# KRP_SMproject_2.net
KiCad netlist of a schematic drawn in EAGLE
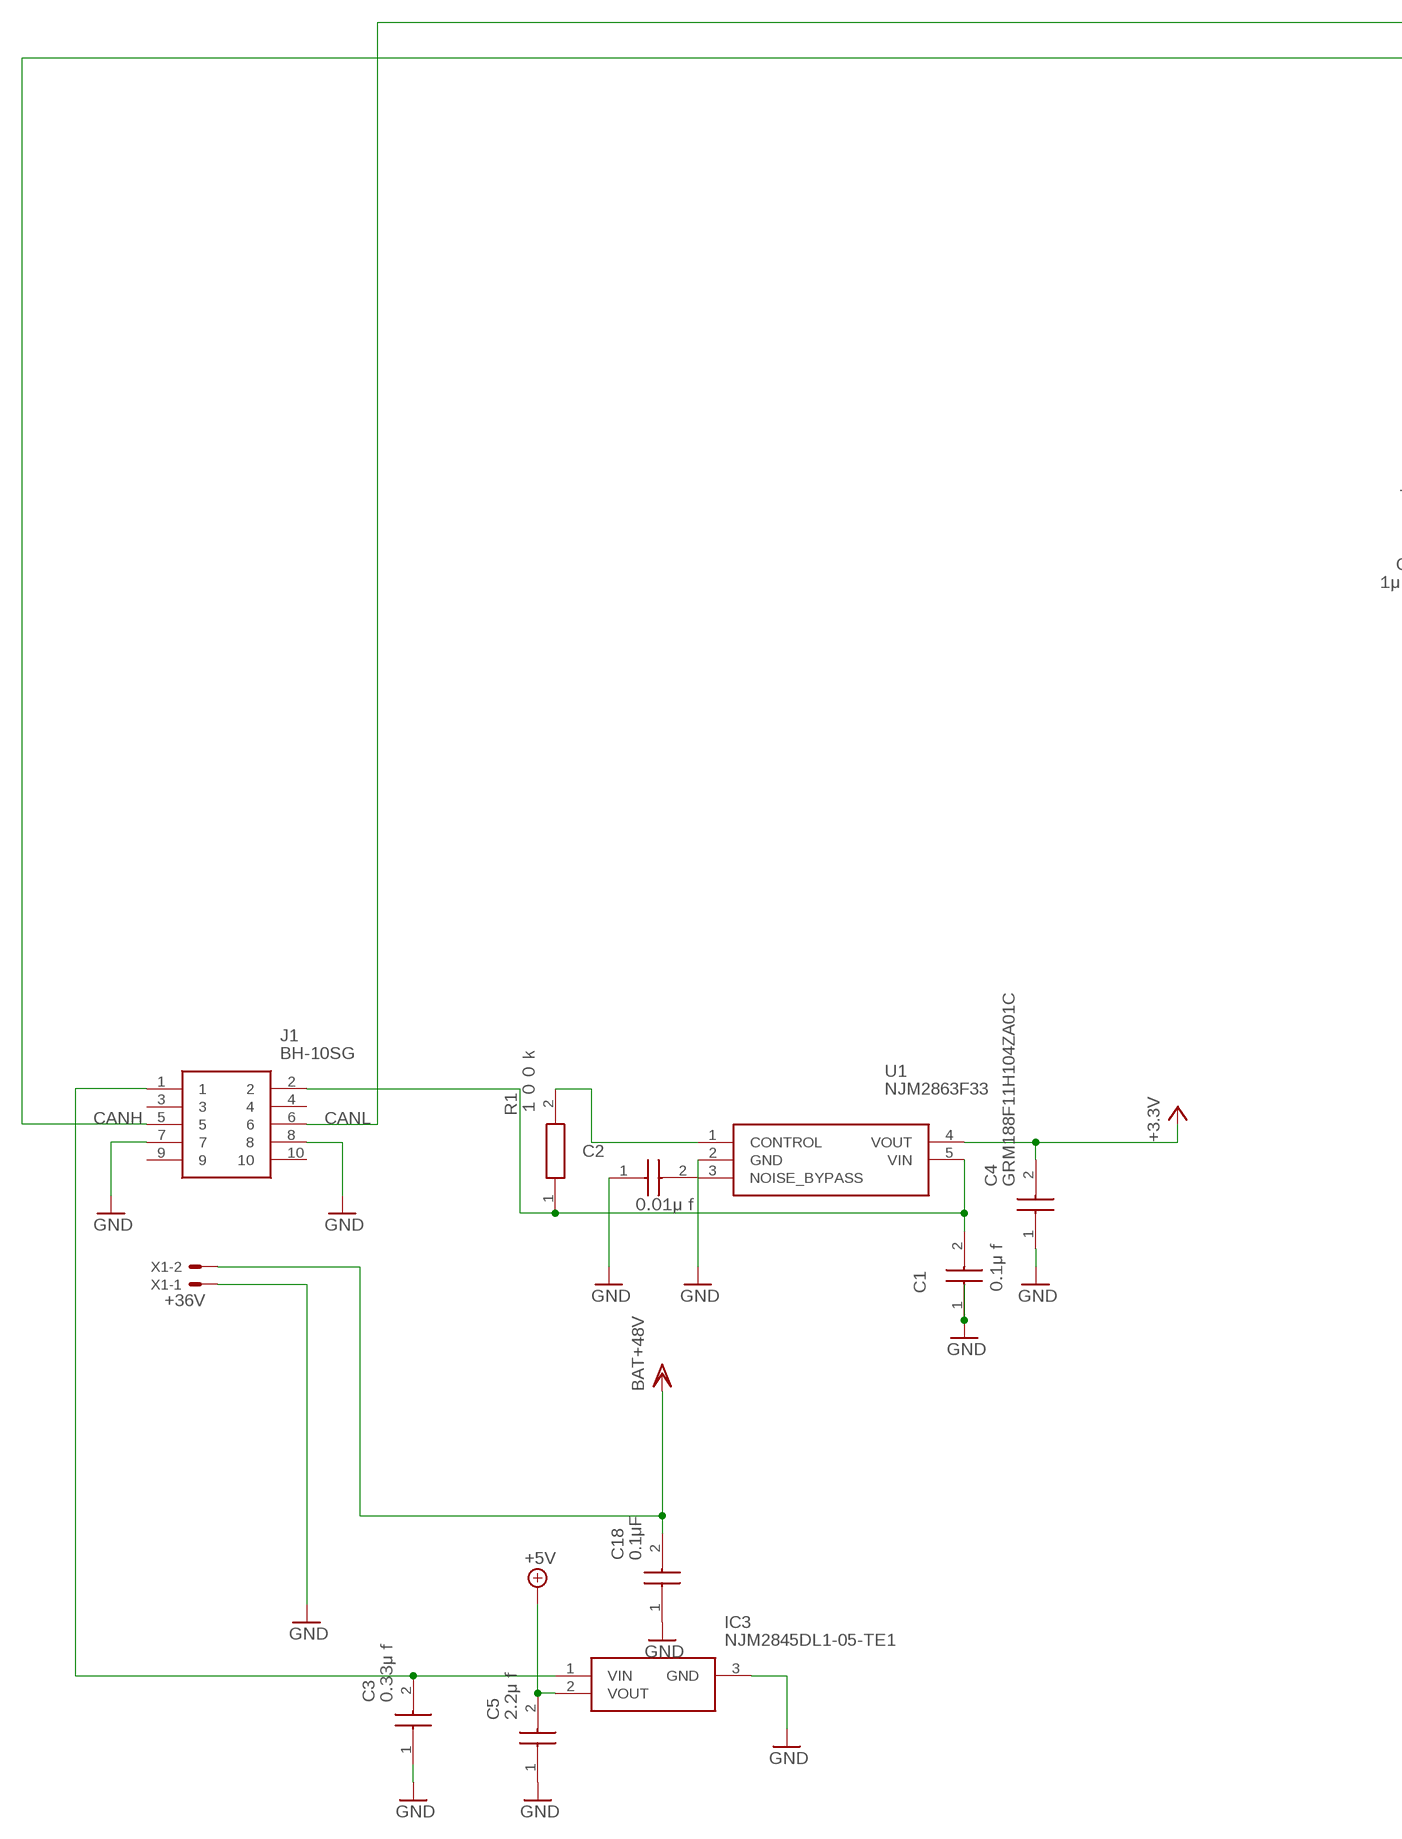
[diagram p0: schematic, sheet 1, part 1 of 2]
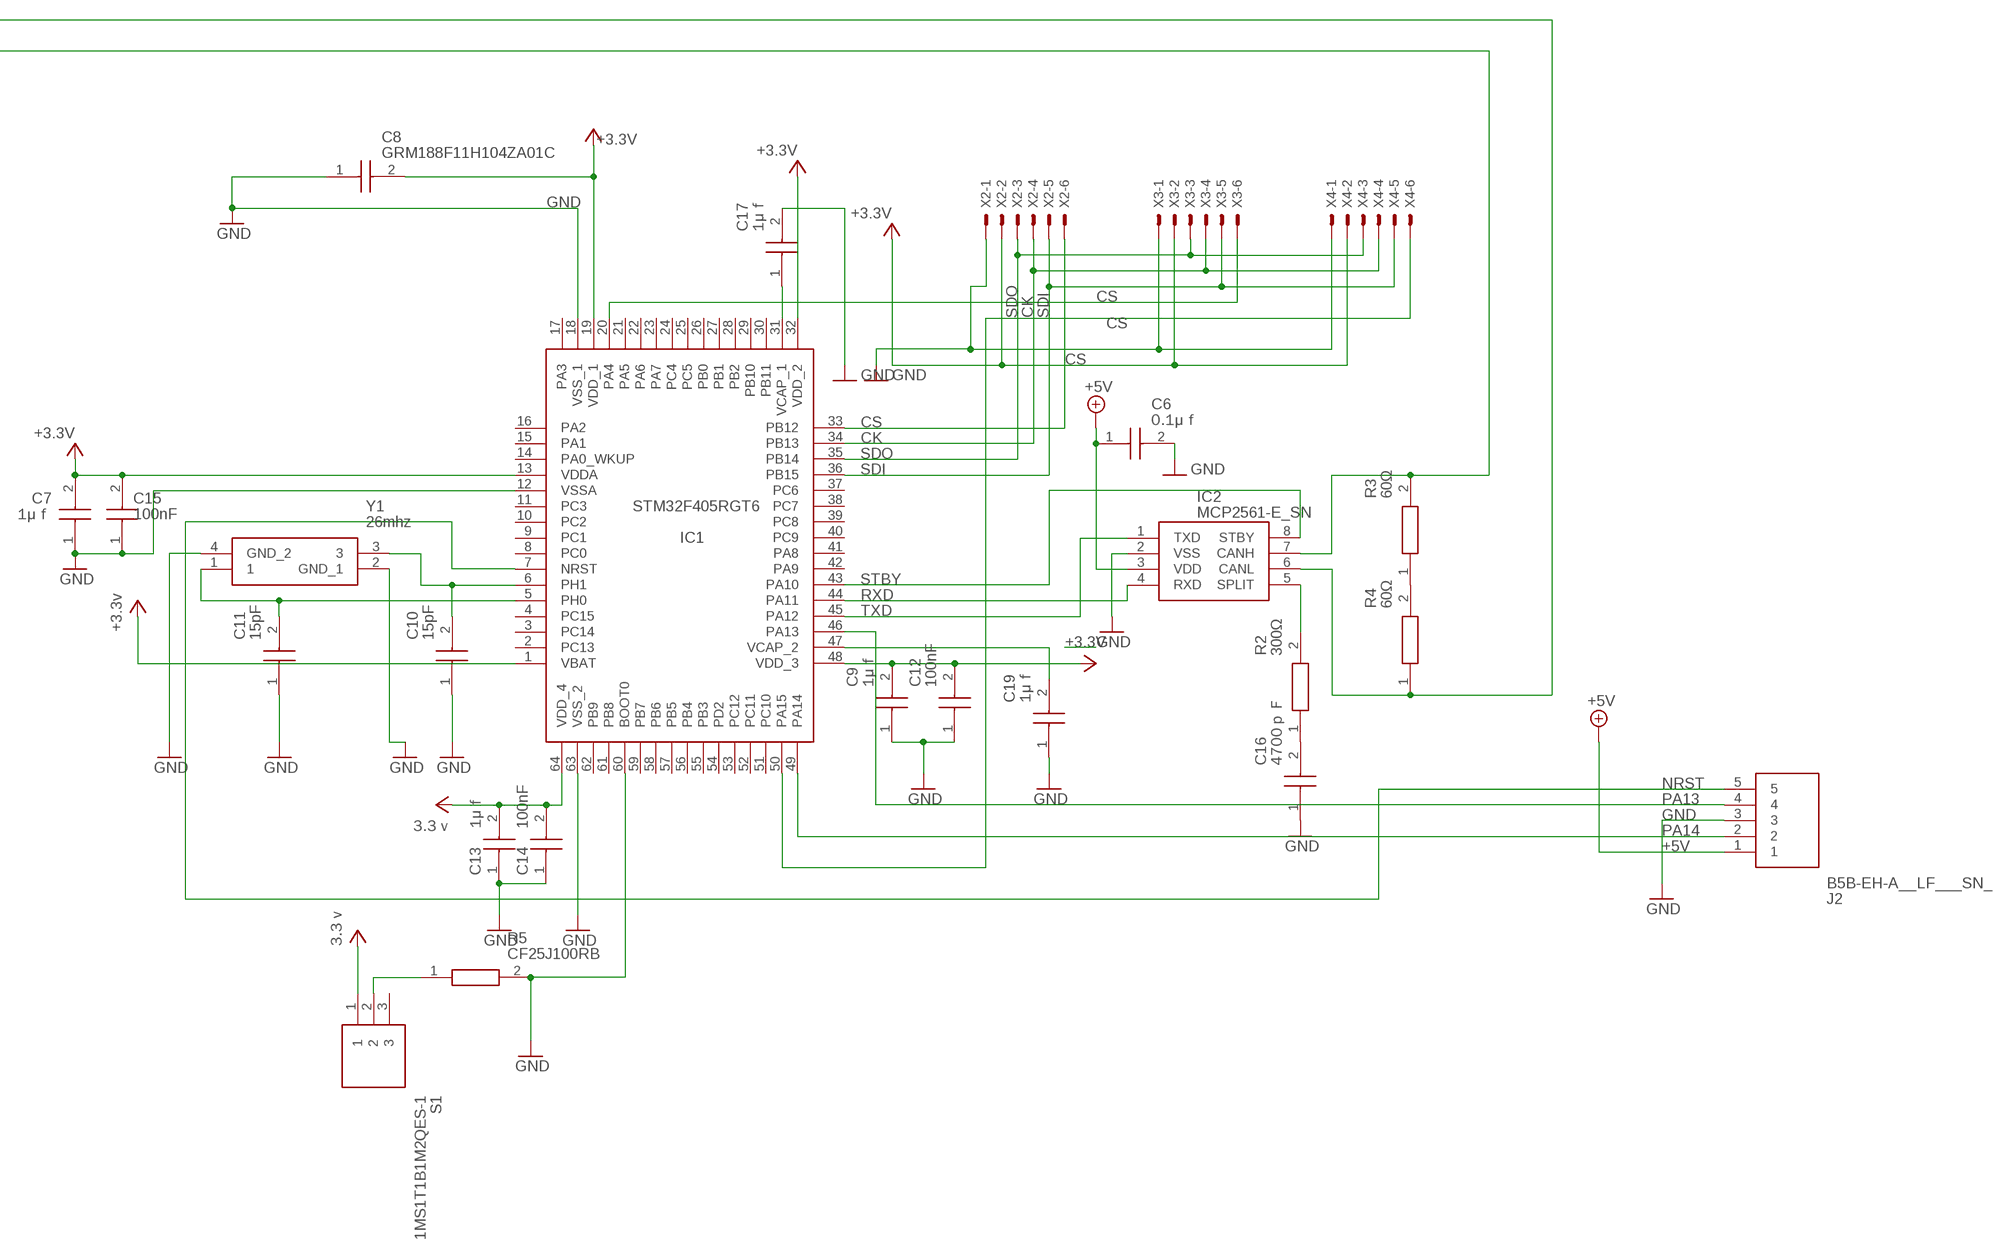
[diagram p1: schematic, sheet 1, part 2 of 2]

(export (version "E")
  (design (tool "Eeschema 10.0.6"))
  (components
    (comp (ref "C1")
      (value "0.1μｆ")
      (footprint "eagle-import:CAPC1608X90N")
      (fields (field (name "MANUFACTURER_PART_NUMBER") "GRM188F11H104ZA01C"))
      (libsource (lib "eagle-import") (part "GRM188F11H104ZA01C"))
    )
    (comp (ref "C2")
      (value "0.01μｆ")
      (footprint "eagle-import:CAPC1608X90N")
      (fields (field (name "MANUFACTURER_PART_NUMBER") "GRM188F11H104ZA01C"))
      (libsource (lib "eagle-import") (part "GRM188F11H104ZA01C"))
    )
    (comp (ref "C3")
      (value "0.33μｆ")
      (footprint "eagle-import:CAPC1608X90N")
      (fields (field (name "MANUFACTURER_PART_NUMBER") "GRM188F11H104ZA01C"))
      (libsource (lib "eagle-import") (part "GRM188F11H104ZA01C"))
    )
    (comp (ref "C4")
      (value "GRM188F11H104ZA01C")
      (footprint "eagle-import:CAPC1608X90N")
      (libsource (lib "eagle-import") (part "GRM188F11H104ZA01C"))
    )
    (comp (ref "C5")
      (value "2.2μｆ")
      (footprint "eagle-import:CAPC1608X90N")
      (fields (field (name "MANUFACTURER_PART_NUMBER") "GRM188F11H104ZA01C"))
      (libsource (lib "eagle-import") (part "GRM188F11H104ZA01C"))
    )
    (comp (ref "C6")
      (value "0.1μｆ")
      (footprint "eagle-import:CAPC1608X90N")
      (fields (field (name "MANUFACTURER_PART_NUMBER") "GRM188F11H104ZA01C"))
      (libsource (lib "eagle-import") (part "GRM188F11H104ZA01C"))
    )
    (comp (ref "C7")
      (value "1μｆ")
      (footprint "eagle-import:CAPC1608X90N")
      (fields (field (name "MANUFACTURER_PART_NUMBER") "GRM188F11H104ZA01C"))
      (libsource (lib "eagle-import") (part "GRM188F11H104ZA01C"))
    )
    (comp (ref "C8")
      (value "GRM188F11H104ZA01C")
      (footprint "eagle-import:CAPC1608X90N")
      (libsource (lib "eagle-import") (part "GRM188F11H104ZA01C"))
    )
    (comp (ref "C9")
      (value "1μｆ")
      (footprint "eagle-import:CAPC1608X90N")
      (fields (field (name "MANUFACTURER_PART_NUMBER") "GRM188F11H104ZA01C"))
      (libsource (lib "eagle-import") (part "GRM188F11H104ZA01C"))
    )
    (comp (ref "C10")
      (value "15pF")
      (footprint "eagle-import:CAPC1608X90N")
      (fields (field (name "MANUFACTURER_PART_NUMBER") "GRM188F11H104ZA01C"))
      (libsource (lib "eagle-import") (part "GRM188F11H104ZA01C"))
    )
    (comp (ref "C11")
      (value "15pF")
      (footprint "eagle-import:CAPC1608X90N")
      (fields (field (name "MANUFACTURER_PART_NUMBER") "GRM188F11H104ZA01C"))
      (libsource (lib "eagle-import") (part "GRM188F11H104ZA01C"))
    )
    (comp (ref "C12")
      (value "100nF")
      (footprint "eagle-import:CAPC1608X90N")
      (fields (field (name "MANUFACTURER_PART_NUMBER") "GRM188F11H104ZA01C"))
      (libsource (lib "eagle-import") (part "GRM188F11H104ZA01C"))
    )
    (comp (ref "C13")
      (value "1μｆ")
      (footprint "eagle-import:CAPC1608X90N")
      (fields (field (name "MANUFACTURER_PART_NUMBER") "GRM188F11H104ZA01C"))
      (libsource (lib "eagle-import") (part "GRM188F11H104ZA01C"))
    )
    (comp (ref "C14")
      (value "100nF")
      (footprint "eagle-import:CAPC1608X90N")
      (fields (field (name "MANUFACTURER_PART_NUMBER") "GRM188F11H104ZA01C"))
      (libsource (lib "eagle-import") (part "GRM188F11H104ZA01C"))
    )
    (comp (ref "C15")
      (value "100nF")
      (footprint "eagle-import:CAPC1608X90N")
      (fields (field (name "MANUFACTURER_PART_NUMBER") "GRM188F11H104ZA01C"))
      (libsource (lib "eagle-import") (part "GRM188F11H104ZA01C"))
    )
    (comp (ref "C16")
      (value "4700ｐＦ")
      (footprint "eagle-import:CAPC1608X90N")
      (fields (field (name "MANUFACTURER_PART_NUMBER") "GRM188F11H104ZA01C"))
      (libsource (lib "eagle-import") (part "GRM188F11H104ZA01C"))
    )
    (comp (ref "C17")
      (value "1μｆ")
      (footprint "eagle-import:CAPC1608X90N")
      (fields (field (name "MANUFACTURER_PART_NUMBER") "GRM188F11H104ZA01C"))
      (libsource (lib "eagle-import") (part "GRM188F11H104ZA01C"))
    )
    (comp (ref "C18")
      (value "0.1μF")
      (footprint "eagle-import:CAPC1608X90N")
      (fields (field (name "MANUFACTURER_PART_NUMBER") "GRM188F11H104ZA01C"))
      (libsource (lib "eagle-import") (part "GRM188F11H104ZA01C"))
    )
    (comp (ref "C19")
      (value "1μｆ")
      (footprint "eagle-import:CAPC1608X90N")
      (fields (field (name "MANUFACTURER_PART_NUMBER") "GRM188F11H104ZA01C"))
      (libsource (lib "eagle-import") (part "GRM188F11H104ZA01C"))
    )
    (comp (ref "IC1")
      (value "STM32F405RGT6")
      (footprint "eagle-import:QFP50P1200X1200X160-64N")
      (fields (field (name "RS_PART_NUMBER") "7468217P"))
      (libsource (lib "eagle-import") (part "STM32F405RGT6"))
    )
    (comp (ref "IC2")
      (value "MCP2561-E_SN")
      (footprint "eagle-import:SOIC127P600X175-8N")
      (fields
        (field (name "MANUFACTURER_PART_NUMBER") "MCP2561-E/SN")
        (field (name "RS_PART_NUMBER") "7990216P")
      )
      (libsource (lib "eagle-import") (part "MCP2561-E_SN"))
    )
    (comp (ref "IC3")
      (value "NJM2845DL1-05-TE1")
      (footprint "eagle-import:TO-252-3-L1")
      (libsource (lib "eagle-import") (part "NJM2845DL1-05-TE1"))
    )
    (comp (ref "J1")
      (value "BH-10SG")
      (footprint "eagle-import:SHDR10W64P254_2X5_2032X910X935")
      (libsource (lib "eagle-import") (part "BH-10SG"))
    )
    (comp (ref "J2")
      (value "B5B-EH-A__LF___SN_")
      (footprint "eagle-import:SHDR5W64P0X250_1X5_1500X380X60")
      (fields
        (field (name "MANUFACTURER_PART_NUMBER") "B5B-EH-A (LF) (SN)")
        (field (name "RS_PART_NUMBER") "5151412P")
      )
      (libsource (lib "eagle-import") (part "B5B-EH-A__LF___SN_"))
    )
    (comp (ref "R1")
      (value "１００ｋ")
      (footprint "eagle-import:RESC1608X50N")
      (fields
        (field (name "MANUFACTURER_PART_NUMBER") "RG1608N-101-W-T1")
        (field (name "RS_PART_NUMBER") "0160452")
      )
      (libsource (lib "eagle-import") (part "RG1608N-101-W-T1"))
    )
    (comp (ref "R2")
      (value "300Ω")
      (footprint "eagle-import:RESC1608X50N")
      (fields
        (field (name "MANUFACTURER_PART_NUMBER") "RG1608N-101-W-T1")
        (field (name "RS_PART_NUMBER") "0160452")
      )
      (libsource (lib "eagle-import") (part "RG1608N-101-W-T1"))
    )
    (comp (ref "R3")
      (value "60Ω")
      (footprint "eagle-import:RESC1608X50N")
      (fields
        (field (name "MANUFACTURER_PART_NUMBER") "RG1608N-101-W-T1")
        (field (name "RS_PART_NUMBER") "0160452")
      )
      (libsource (lib "eagle-import") (part "RG1608N-101-W-T1"))
    )
    (comp (ref "R4")
      (value "60Ω")
      (footprint "eagle-import:RESC1608X50N")
      (fields
        (field (name "MANUFACTURER_PART_NUMBER") "RG1608N-101-W-T1")
        (field (name "RS_PART_NUMBER") "0160452")
      )
      (libsource (lib "eagle-import") (part "RG1608N-101-W-T1"))
    )
    (comp (ref "R5")
      (value "CF25J100RB")
      (footprint "eagle-import:RESAD1550W60L630D230")
      (libsource (lib "eagle-import") (part "CF25J100RB"))
    )
    (comp (ref "S1")
      (value "1MS1T1B1M2QES-1")
      (footprint "eagle-import:1MS1T1B1M2QES-5")
      (libsource (lib "eagle-import") (part "1MS1T1B1M2QES-1"))
    )
    (comp (ref "U1")
      (value "NJM2863F33")
      (footprint "eagle-import:SOT95P280X130-5N")
      (libsource (lib "eagle-import") (part "NJM2863F33"))
    )
    (comp (ref "X1")
      (value "+36V")
      (footprint "eagle-import:22-23-2021")
      (fields (field (name "MF") "MOLEX") (field (name "MPN") "22-23-2021"))
      (libsource (lib "eagle-import") (part "22-23-2021"))
    )
    (comp (ref "X2")
      (value "22-23-2061")
      (footprint "eagle-import:22-23-2061")
      (fields (field (name "MF") "MOLEX"))
      (libsource (lib "eagle-import") (part "22-23-2061"))
    )
    (comp (ref "X3")
      (value "22-23-2061")
      (footprint "eagle-import:22-23-2061")
      (fields (field (name "MF") "MOLEX"))
      (libsource (lib "eagle-import") (part "22-23-2061"))
    )
    (comp (ref "X4")
      (value "22-23-2061")
      (footprint "eagle-import:22-23-2061")
      (fields (field (name "MF") "MOLEX"))
      (libsource (lib "eagle-import") (part "22-23-2061"))
    )
    (comp (ref "Y1")
      (value "26mhz")
      (footprint "eagle-import:FA128")
      (fields (field (name "MANUFACTURER_PART_NUMBER") "FA-128 32.0000MF20X-K3"))
      (libsource (lib "eagle-import") (part "FA-128_32.0000MF20X-K3"))
    )
  )
  (nets
    (net (code "1") (name "+3.3V") (class "Default")
      (node (ref "C12") (pin "2") (pinfunction "2_2") (pintype "bidirectional"))
      (node (ref "C13") (pin "2") (pinfunction "2_2") (pintype "bidirectional"))
      (node (ref "C14") (pin "2") (pinfunction "2_2") (pintype "bidirectional"))
      (node (ref "C15") (pin "2") (pinfunction "2_2") (pintype "bidirectional"))
      (node (ref "C4") (pin "2") (pinfunction "2_2") (pintype "bidirectional"))
      (node (ref "C5") (pin "2") (pinfunction "2_2") (pintype "bidirectional"))
      (node (ref "C6") (pin "1") (pinfunction "1_1") (pintype "bidirectional"))
      (node (ref "C7") (pin "2") (pinfunction "2_2") (pintype "bidirectional"))
      (node (ref "C8") (pin "2") (pinfunction "2_2") (pintype "bidirectional"))
      (node (ref "C9") (pin "2") (pinfunction "2_2") (pintype "bidirectional"))
      (node (ref "IC1") (pin "1") (pinfunction "VBAT_1") (pintype "bidirectional"))
      (node (ref "IC1") (pin "13") (pinfunction "VDDA_13") (pintype "power_in"))
      (node (ref "IC1") (pin "19") (pinfunction "VDD_1_19") (pintype "power_in"))
      (node (ref "IC1") (pin "32") (pinfunction "VDD_2_32") (pintype "power_in"))
      (node (ref "IC1") (pin "48") (pinfunction "VDD_3_48") (pintype "power_in"))
      (node (ref "IC1") (pin "64") (pinfunction "VDD_4_64") (pintype "power_in"))
      (node (ref "IC2") (pin "3") (pinfunction "VDD_3") (pintype "bidirectional"))
      (node (ref "IC3") (pin "2") (pinfunction "VOUT_2") (pintype "bidirectional"))
      (node (ref "J2") (pin "1") (pinfunction "1_1") (pintype "bidirectional"))
      (node (ref "S1") (pin "1") (pinfunction "1_1") (pintype "bidirectional"))
      (node (ref "U1") (pin "4") (pinfunction "VOUT_4") (pintype "bidirectional"))
      (node (ref "X2") (pin "2") (pinfunction "S_2") (pintype "passive"))
      (node (ref "X3") (pin "2") (pinfunction "S_2") (pintype "passive"))
      (node (ref "X4") (pin "2") (pinfunction "S_2") (pintype "passive"))
    )
    (net (code "2") (name "/CANH") (class "Default")
      (node (ref "IC2") (pin "7") (pinfunction "CANH_7") (pintype "bidirectional"))
      (node (ref "J1") (pin "5") (pinfunction "5_5") (pintype "bidirectional"))
      (node (ref "R3") (pin "2") (pinfunction "2_2") (pintype "bidirectional"))
    )
    (net (code "3") (name "/CANL") (class "Default")
      (node (ref "IC2") (pin "6") (pinfunction "CANL_6") (pintype "bidirectional"))
      (node (ref "J1") (pin "6") (pinfunction "6_6") (pintype "bidirectional"))
      (node (ref "R4") (pin "1") (pinfunction "1_1") (pintype "bidirectional"))
    )
    (net (code "4") (name "/CK") (class "Default")
      (node (ref "IC1") (pin "34") (pinfunction "PB13_34") (pintype "bidirectional"))
      (node (ref "X2") (pin "4") (pinfunction "S_4") (pintype "passive"))
      (node (ref "X3") (pin "4") (pinfunction "S_4") (pintype "passive"))
      (node (ref "X4") (pin "4") (pinfunction "S_4") (pintype "passive"))
    )
    (net (code "5") (name "/CS") (class "Default")
      (node (ref "IC1") (pin "20") (pinfunction "PA4_20") (pintype "bidirectional"))
      (node (ref "IC1") (pin "33") (pinfunction "PB12_33") (pintype "bidirectional"))
      (node (ref "IC1") (pin "50") (pinfunction "PA15_50") (pintype "bidirectional"))
      (node (ref "X2") (pin "6") (pinfunction "S_6") (pintype "passive"))
      (node (ref "X3") (pin "6") (pinfunction "S_6") (pintype "passive"))
      (node (ref "X4") (pin "6") (pinfunction "S_6") (pintype "passive"))
    )
    (net (code "6") (name "/NRST") (class "Default")
      (node (ref "IC1") (pin "7") (pinfunction "NRST_7") (pintype "input"))
      (node (ref "J2") (pin "5") (pinfunction "5_5") (pintype "bidirectional"))
    )
    (net (code "7") (name "/PA13") (class "Default")
      (node (ref "IC1") (pin "46") (pinfunction "PA13_46") (pintype "bidirectional"))
      (node (ref "J2") (pin "4") (pinfunction "4_4") (pintype "bidirectional"))
    )
    (net (code "8") (name "/PA14") (class "Default")
      (node (ref "IC1") (pin "49") (pinfunction "PA14_49") (pintype "bidirectional"))
      (node (ref "J2") (pin "2") (pinfunction "2_2") (pintype "bidirectional"))
    )
    (net (code "9") (name "/RXD") (class "Default")
      (node (ref "IC1") (pin "44") (pinfunction "PA11_44") (pintype "bidirectional"))
      (node (ref "IC2") (pin "4") (pinfunction "RXD_4") (pintype "bidirectional"))
    )
    (net (code "10") (name "/SDI") (class "Default")
      (node (ref "IC1") (pin "36") (pinfunction "PB15_36") (pintype "bidirectional"))
      (node (ref "X2") (pin "5") (pinfunction "S_5") (pintype "passive"))
      (node (ref "X3") (pin "5") (pinfunction "S_5") (pintype "passive"))
      (node (ref "X4") (pin "5") (pinfunction "S_5") (pintype "passive"))
    )
    (net (code "11") (name "/SDO") (class "Default")
      (node (ref "IC1") (pin "35") (pinfunction "PB14_35") (pintype "bidirectional"))
      (node (ref "X2") (pin "3") (pinfunction "S_3") (pintype "passive"))
      (node (ref "X3") (pin "3") (pinfunction "S_3") (pintype "passive"))
      (node (ref "X4") (pin "3") (pinfunction "S_3") (pintype "passive"))
    )
    (net (code "12") (name "/STBY") (class "Default")
      (node (ref "IC1") (pin "43") (pinfunction "PA10_43") (pintype "bidirectional"))
      (node (ref "IC2") (pin "8") (pinfunction "STBY_8") (pintype "bidirectional"))
    )
    (net (code "13") (name "/TXD") (class "Default")
      (node (ref "IC1") (pin "45") (pinfunction "PA12_45") (pintype "bidirectional"))
      (node (ref "IC2") (pin "1") (pinfunction "TXD_1") (pintype "bidirectional"))
    )
    (net (code "14") (name "BAT+48V") (class "Default")
      (node (ref "C18") (pin "2") (pinfunction "2_2") (pintype "bidirectional"))
      (node (ref "X1") (pin "2") (pinfunction "S_2") (pintype "passive"))
    )
    (net (code "15") (name "GND") (class "Default")
      (node (ref "C1") (pin "1") (pinfunction "1_1") (pintype "bidirectional"))
      (node (ref "C10") (pin "1") (pinfunction "1_1") (pintype "bidirectional"))
      (node (ref "C11") (pin "1") (pinfunction "1_1") (pintype "bidirectional"))
      (node (ref "C12") (pin "1") (pinfunction "1_1") (pintype "bidirectional"))
      (node (ref "C13") (pin "1") (pinfunction "1_1") (pintype "bidirectional"))
      (node (ref "C14") (pin "1") (pinfunction "1_1") (pintype "bidirectional"))
      (node (ref "C15") (pin "1") (pinfunction "1_1") (pintype "bidirectional"))
      (node (ref "C16") (pin "1") (pinfunction "1_1") (pintype "bidirectional"))
      (node (ref "C17") (pin "2") (pinfunction "2_2") (pintype "bidirectional"))
      (node (ref "C18") (pin "1") (pinfunction "1_1") (pintype "bidirectional"))
      (node (ref "C19") (pin "1") (pinfunction "1_1") (pintype "bidirectional"))
      (node (ref "C2") (pin "1") (pinfunction "1_1") (pintype "bidirectional"))
      (node (ref "C3") (pin "1") (pinfunction "1_1") (pintype "bidirectional"))
      (node (ref "C4") (pin "1") (pinfunction "1_1") (pintype "bidirectional"))
      (node (ref "C5") (pin "1") (pinfunction "1_1") (pintype "bidirectional"))
      (node (ref "C6") (pin "2") (pinfunction "2_2") (pintype "bidirectional"))
      (node (ref "C7") (pin "1") (pinfunction "1_1") (pintype "bidirectional"))
      (node (ref "C8") (pin "1") (pinfunction "1_1") (pintype "bidirectional"))
      (node (ref "C9") (pin "1") (pinfunction "1_1") (pintype "bidirectional"))
      (node (ref "IC1") (pin "12") (pinfunction "VSSA_12") (pintype "power_in"))
      (node (ref "IC1") (pin "18") (pinfunction "VSS_1_18") (pintype "power_in"))
      (node (ref "IC1") (pin "60") (pinfunction "BOOT0_60") (pintype "bidirectional"))
      (node (ref "IC1") (pin "63") (pinfunction "VSS_2_63") (pintype "power_in"))
      (node (ref "IC2") (pin "2") (pinfunction "VSS_2") (pintype "bidirectional"))
      (node (ref "IC3") (pin "3") (pinfunction "GND_3") (pintype "bidirectional"))
      (node (ref "J1") (pin "7") (pinfunction "7_7") (pintype "bidirectional"))
      (node (ref "J1") (pin "8") (pinfunction "8_8") (pintype "bidirectional"))
      (node (ref "J2") (pin "3") (pinfunction "3_3") (pintype "bidirectional"))
      (node (ref "R5") (pin "2") (pinfunction "2_2") (pintype "bidirectional"))
      (node (ref "U1") (pin "2") (pinfunction "GND_2") (pintype "bidirectional"))
      (node (ref "X1") (pin "1") (pinfunction "S_1") (pintype "passive"))
      (node (ref "X2") (pin "1") (pinfunction "S_1") (pintype "passive"))
      (node (ref "X3") (pin "1") (pinfunction "S_1") (pintype "passive"))
      (node (ref "X4") (pin "1") (pinfunction "S_1") (pintype "passive"))
      (node (ref "Y1") (pin "2") (pinfunction "GND_1_2") (pintype "bidirectional"))
      (node (ref "Y1") (pin "4") (pinfunction "GND_2_4") (pintype "bidirectional"))
    )
    (net (code "16") (name "Net-(C16-Pad2)") (class "Default")
      (node (ref "C16") (pin "2") (pinfunction "2_2") (pintype "bidirectional"))
      (node (ref "R2") (pin "1") (pinfunction "1_1") (pintype "bidirectional"))
    )
    (net (code "17") (name "Net-(IC1-PH0)") (class "Default")
      (node (ref "C11") (pin "2") (pinfunction "2_2") (pintype "bidirectional"))
      (node (ref "IC1") (pin "5") (pinfunction "PH0_5") (pintype "bidirectional"))
      (node (ref "Y1") (pin "1") (pinfunction "1_1") (pintype "bidirectional"))
    )
    (net (code "18") (name "Net-(IC1-PH1)") (class "Default")
      (node (ref "C10") (pin "2") (pinfunction "2_2") (pintype "bidirectional"))
      (node (ref "IC1") (pin "6") (pinfunction "PH1_6") (pintype "bidirectional"))
      (node (ref "Y1") (pin "3") (pinfunction "3_3") (pintype "bidirectional"))
    )
    (net (code "19") (name "Net-(IC1-VCAP_1)") (class "Default")
      (node (ref "C17") (pin "1") (pinfunction "1_1") (pintype "bidirectional"))
      (node (ref "IC1") (pin "31") (pinfunction "VCAP_1_31") (pintype "bidirectional"))
    )
    (net (code "20") (name "Net-(IC1-VCAP_2)") (class "Default")
      (node (ref "C19") (pin "2") (pinfunction "2_2") (pintype "bidirectional"))
      (node (ref "IC1") (pin "47") (pinfunction "VCAP_2_47") (pintype "bidirectional"))
    )
    (net (code "21") (name "Net-(IC2-SPLIT)") (class "Default")
      (node (ref "IC2") (pin "5") (pinfunction "SPLIT_5") (pintype "bidirectional"))
      (node (ref "R2") (pin "2") (pinfunction "2_2") (pintype "bidirectional"))
    )
    (net (code "22") (name "Net-(IC3-VIN)") (class "Default")
      (node (ref "C3") (pin "2") (pinfunction "2_2") (pintype "bidirectional"))
      (node (ref "IC3") (pin "1") (pinfunction "VIN_1") (pintype "bidirectional"))
      (node (ref "J1") (pin "1") (pinfunction "1_1") (pintype "bidirectional"))
    )
    (net (code "23") (name "Net-(R3-Pad1)") (class "Default")
      (node (ref "R3") (pin "1") (pinfunction "1_1") (pintype "bidirectional"))
      (node (ref "R4") (pin "2") (pinfunction "2_2") (pintype "bidirectional"))
    )
    (net (code "24") (name "Net-(R5-Pad1)") (class "Default")
      (node (ref "R5") (pin "1") (pinfunction "1_1") (pintype "bidirectional"))
      (node (ref "S1") (pin "2") (pinfunction "2_2") (pintype "bidirectional"))
    )
    (net (code "25") (name "Net-(U1-CONTROL)") (class "Default")
      (node (ref "R1") (pin "2") (pinfunction "2_2") (pintype "bidirectional"))
      (node (ref "U1") (pin "1") (pinfunction "CONTROL_1") (pintype "bidirectional"))
    )
    (net (code "26") (name "Net-(U1-NOISE_BYPASS)") (class "Default")
      (node (ref "C2") (pin "2") (pinfunction "2_2") (pintype "bidirectional"))
      (node (ref "U1") (pin "3") (pinfunction "NOISE_BYPASS_3") (pintype "bidirectional"))
    )
    (net (code "27") (name "Net-(U1-VIN)") (class "Default")
      (node (ref "C1") (pin "2") (pinfunction "2_2") (pintype "bidirectional"))
      (node (ref "J1") (pin "2") (pinfunction "2_2") (pintype "bidirectional"))
      (node (ref "R1") (pin "1") (pinfunction "1_1") (pintype "bidirectional"))
      (node (ref "U1") (pin "5") (pinfunction "VIN_5") (pintype "bidirectional"))
    )
    (net (code "28") (name "unconnected-(IC1-PA0_WKUP-Pad14)") (class "Default")
      (node (ref "IC1") (pin "14") (pinfunction "PA0_WKUP_14") (pintype "bidirectional"))
    )
    (net (code "29") (name "unconnected-(IC1-PA1-Pad15)") (class "Default")
      (node (ref "IC1") (pin "15") (pinfunction "PA1_15") (pintype "bidirectional"))
    )
    (net (code "30") (name "unconnected-(IC1-PA2-Pad16)") (class "Default")
      (node (ref "IC1") (pin "16") (pinfunction "PA2_16") (pintype "bidirectional"))
    )
    (net (code "31") (name "unconnected-(IC1-PA3-Pad17)") (class "Default")
      (node (ref "IC1") (pin "17") (pinfunction "PA3_17") (pintype "bidirectional"))
    )
    (net (code "32") (name "unconnected-(IC1-PA5-Pad21)") (class "Default")
      (node (ref "IC1") (pin "21") (pinfunction "PA5_21") (pintype "bidirectional"))
    )
    (net (code "33") (name "unconnected-(IC1-PA6-Pad22)") (class "Default")
      (node (ref "IC1") (pin "22") (pinfunction "PA6_22") (pintype "bidirectional"))
    )
    (net (code "34") (name "unconnected-(IC1-PA7-Pad23)") (class "Default")
      (node (ref "IC1") (pin "23") (pinfunction "PA7_23") (pintype "bidirectional"))
    )
    (net (code "35") (name "unconnected-(IC1-PA8-Pad41)") (class "Default")
      (node (ref "IC1") (pin "41") (pinfunction "PA8_41") (pintype "bidirectional"))
    )
    (net (code "36") (name "unconnected-(IC1-PA9-Pad42)") (class "Default")
      (node (ref "IC1") (pin "42") (pinfunction "PA9_42") (pintype "bidirectional"))
    )
    (net (code "37") (name "unconnected-(IC1-PB0-Pad26)") (class "Default")
      (node (ref "IC1") (pin "26") (pinfunction "PB0_26") (pintype "bidirectional"))
    )
    (net (code "38") (name "unconnected-(IC1-PB1-Pad27)") (class "Default")
      (node (ref "IC1") (pin "27") (pinfunction "PB1_27") (pintype "bidirectional"))
    )
    (net (code "39") (name "unconnected-(IC1-PB2-Pad28)") (class "Default")
      (node (ref "IC1") (pin "28") (pinfunction "PB2_28") (pintype "bidirectional"))
    )
    (net (code "40") (name "unconnected-(IC1-PB3-Pad55)") (class "Default")
      (node (ref "IC1") (pin "55") (pinfunction "PB3_55") (pintype "bidirectional"))
    )
    (net (code "41") (name "unconnected-(IC1-PB4-Pad56)") (class "Default")
      (node (ref "IC1") (pin "56") (pinfunction "PB4_56") (pintype "bidirectional"))
    )
    (net (code "42") (name "unconnected-(IC1-PB5-Pad57)") (class "Default")
      (node (ref "IC1") (pin "57") (pinfunction "PB5_57") (pintype "bidirectional"))
    )
    (net (code "43") (name "unconnected-(IC1-PB6-Pad58)") (class "Default")
      (node (ref "IC1") (pin "58") (pinfunction "PB6_58") (pintype "bidirectional"))
    )
    (net (code "44") (name "unconnected-(IC1-PB7-Pad59)") (class "Default")
      (node (ref "IC1") (pin "59") (pinfunction "PB7_59") (pintype "bidirectional"))
    )
    (net (code "45") (name "unconnected-(IC1-PB8-Pad61)") (class "Default")
      (node (ref "IC1") (pin "61") (pinfunction "PB8_61") (pintype "bidirectional"))
    )
    (net (code "46") (name "unconnected-(IC1-PB9-Pad62)") (class "Default")
      (node (ref "IC1") (pin "62") (pinfunction "PB9_62") (pintype "bidirectional"))
    )
    (net (code "47") (name "unconnected-(IC1-PB10-Pad29)") (class "Default")
      (node (ref "IC1") (pin "29") (pinfunction "PB10_29") (pintype "bidirectional"))
    )
    (net (code "48") (name "unconnected-(IC1-PB11-Pad30)") (class "Default")
      (node (ref "IC1") (pin "30") (pinfunction "PB11_30") (pintype "bidirectional"))
    )
    (net (code "49") (name "unconnected-(IC1-PC0-Pad8)") (class "Default")
      (node (ref "IC1") (pin "8") (pinfunction "PC0_8") (pintype "bidirectional"))
    )
    (net (code "50") (name "unconnected-(IC1-PC1-Pad9)") (class "Default")
      (node (ref "IC1") (pin "9") (pinfunction "PC1_9") (pintype "bidirectional"))
    )
    (net (code "51") (name "unconnected-(IC1-PC2-Pad10)") (class "Default")
      (node (ref "IC1") (pin "10") (pinfunction "PC2_10") (pintype "bidirectional"))
    )
    (net (code "52") (name "unconnected-(IC1-PC3-Pad11)") (class "Default")
      (node (ref "IC1") (pin "11") (pinfunction "PC3_11") (pintype "bidirectional"))
    )
    (net (code "53") (name "unconnected-(IC1-PC4-Pad24)") (class "Default")
      (node (ref "IC1") (pin "24") (pinfunction "PC4_24") (pintype "bidirectional"))
    )
    (net (code "54") (name "unconnected-(IC1-PC5-Pad25)") (class "Default")
      (node (ref "IC1") (pin "25") (pinfunction "PC5_25") (pintype "bidirectional"))
    )
    (net (code "55") (name "unconnected-(IC1-PC6-Pad37)") (class "Default")
      (node (ref "IC1") (pin "37") (pinfunction "PC6_37") (pintype "bidirectional"))
    )
    (net (code "56") (name "unconnected-(IC1-PC7-Pad38)") (class "Default")
      (node (ref "IC1") (pin "38") (pinfunction "PC7_38") (pintype "bidirectional"))
    )
    (net (code "57") (name "unconnected-(IC1-PC8-Pad39)") (class "Default")
      (node (ref "IC1") (pin "39") (pinfunction "PC8_39") (pintype "bidirectional"))
    )
    (net (code "58") (name "unconnected-(IC1-PC9-Pad40)") (class "Default")
      (node (ref "IC1") (pin "40") (pinfunction "PC9_40") (pintype "bidirectional"))
    )
    (net (code "59") (name "unconnected-(IC1-PC10-Pad51)") (class "Default")
      (node (ref "IC1") (pin "51") (pinfunction "PC10_51") (pintype "bidirectional"))
    )
    (net (code "60") (name "unconnected-(IC1-PC11-Pad52)") (class "Default")
      (node (ref "IC1") (pin "52") (pinfunction "PC11_52") (pintype "bidirectional"))
    )
    (net (code "61") (name "unconnected-(IC1-PC12-Pad53)") (class "Default")
      (node (ref "IC1") (pin "53") (pinfunction "PC12_53") (pintype "bidirectional"))
    )
    (net (code "62") (name "unconnected-(IC1-PC13-Pad2)") (class "Default")
      (node (ref "IC1") (pin "2") (pinfunction "PC13_2") (pintype "bidirectional"))
    )
    (net (code "63") (name "unconnected-(IC1-PC14-Pad3)") (class "Default")
      (node (ref "IC1") (pin "3") (pinfunction "PC14_3") (pintype "bidirectional"))
    )
    (net (code "64") (name "unconnected-(IC1-PC15-Pad4)") (class "Default")
      (node (ref "IC1") (pin "4") (pinfunction "PC15_4") (pintype "bidirectional"))
    )
    (net (code "65") (name "unconnected-(IC1-PD2-Pad54)") (class "Default")
      (node (ref "IC1") (pin "54") (pinfunction "PD2_54") (pintype "bidirectional"))
    )
    (net (code "66") (name "unconnected-(J1-Pad3)") (class "Default")
      (node (ref "J1") (pin "3") (pinfunction "3_3") (pintype "bidirectional"))
    )
    (net (code "67") (name "unconnected-(J1-Pad4)") (class "Default")
      (node (ref "J1") (pin "4") (pinfunction "4_4") (pintype "bidirectional"))
    )
    (net (code "68") (name "unconnected-(J1-Pad9)") (class "Default")
      (node (ref "J1") (pin "9") (pinfunction "9_9") (pintype "bidirectional"))
    )
    (net (code "69") (name "unconnected-(J1-Pad10)") (class "Default")
      (node (ref "J1") (pin "10") (pinfunction "10_10") (pintype "bidirectional"))
    )
    (net (code "70") (name "unconnected-(S1-Pad3)") (class "Default")
      (node (ref "S1") (pin "3") (pinfunction "3_3") (pintype "bidirectional"))
    )
  )
)
